# Sheet1.net
KiCad netlist of a schematic drawn in Altium Designer
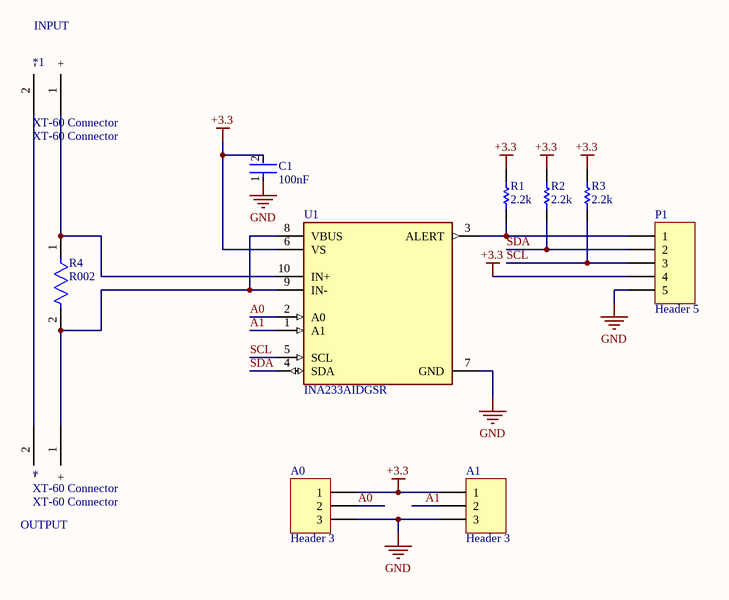
[diagram p0: Sheet1.SchDoc]

(export (version "E")
  (design (tool "Eeschema 10.0.6"))
  (components
    (comp (ref "*")
      (value "XT-60 Connector")
      (footprint "XT-60")
      (fields
        (field (name "MANUFACTURER") "POLOLU")
        (field (name "MANUFACTURER PART NUMBER") "XT60 YELLOW")
        (field (name "SUPPLIER PART NUMBER 1") "XT-60 Connector")
      )
      (libsource (lib "AltiumLibraryDDT") (part "XT-60 Connector"))
    )
    (comp (ref "*1")
      (value "XT-60 Connector")
      (footprint "XT-60")
      (fields
        (field (name "MANUFACTURER") "POLOLU")
        (field (name "MANUFACTURER PART NUMBER") "XT60 YELLOW")
        (field (name "SUPPLIER PART NUMBER 1") "XT-60 Connector")
      )
      (libsource (lib "AltiumLibraryDDT") (part "XT-60 Connector"))
    )
    (comp (ref "A0")
      (value "Header 3")
      (footprint "HDR1X3")
      (description "Header, 3-Pin")
      (fields (field (name "PUBLISHER") "Altium Limited"))
      (libsource (lib "") (part "Header 3_1"))
    )
    (comp (ref "A1")
      (value "Header 3")
      (footprint "HDR1X3")
      (description "Header, 3-Pin")
      (fields (field (name "PUBLISHER") "Altium Limited"))
      (libsource (lib "Miscellaneous Connectors") (part "Header 3"))
    )
    (comp (ref "C1")
      (value "100nF")
      (footprint "FP-0805-L_2_01_0_2-W_1_25-IPC_B")
      (description "General Purpose Ceramic Capacitor, 0805, 100nF, 10%, X7R, 15%, 100V")
      (fields (field (name "VOLTAGE") "100V") (field (name "TOLERANCE") "10%"))
      (libsource (lib "Altium Content Vault") (part "b4654b650e69147ec39a6b967a45e02"))
    )
    (comp (ref "P1")
      (value "Header 5")
      (footprint "HDR1X5")
      (description "Header, 5-Pin")
      (fields (field (name "PUBLISHER") "Altium Limited"))
      (libsource (lib "Miscellaneous Connectors") (part "Header 5"))
    )
    (comp (ref "R1")
      (value "2.2k")
      (footprint "RESC2013X60X35ML10T20")
      (fields (field (name "TOLERANCE") "5%") (field (name "MANUFACTURER") "Yageo"))
      (libsource (lib "Altium Content Vault") (part "RES-2"))
    )
    (comp (ref "R2")
      (value "2.2k")
      (footprint "RESC2013X60X35ML10T20")
      (fields (field (name "TOLERANCE") "5%") (field (name "MANUFACTURER") "Yageo"))
      (libsource (lib "Altium Content Vault") (part "RES-2"))
    )
    (comp (ref "R3")
      (value "2.2k")
      (footprint "RESC2013X60X35ML10T20")
      (fields (field (name "TOLERANCE") "5%") (field (name "MANUFACTURER") "Yageo"))
      (libsource (lib "Altium Content Vault") (part "RES-2"))
    )
    (comp (ref "R4")
      (value "R002")
      (footprint "FP-RL2512-MFG")
      (description "Thick Film Resistors - SMD 0.1ohm 1% 1W")
      (fields (field (name "OCTOPART") "https://octopart.com/rl2512fk-070r1l-yageo-42334369"))
      (libsource (lib "Altium Content Vault") (part "1029c3af85768c4190bb7ad29bc67b5"))
    )
    (comp (ref "U1")
      (value "INA233AIDGSR")
      (footprint "FP-DGS0010A-MFG")
      (libsource (lib "Altium Content Vault") (part "862aca6ea8ed29acc4669ae8acb3e69"))
    )
  )
  (nets
    (net (code "1") (name "+3.3") (class "Default")
      (node (ref "A0") (pin "1") (pinfunction "1_1") (pintype "passive"))
      (node (ref "A1") (pin "1") (pinfunction "1_1") (pintype "passive"))
      (node (ref "C1") (pin "2") (pinfunction "2_2") (pintype "passive"))
      (node (ref "P1") (pin "4") (pinfunction "4_4") (pintype "passive"))
      (node (ref "R1") (pin "2") (pinfunction "2_2") (pintype "passive"))
      (node (ref "R2") (pin "2") (pinfunction "2_2") (pintype "passive"))
      (node (ref "R3") (pin "2") (pinfunction "2_2") (pintype "passive"))
      (node (ref "U1") (pin "6") (pinfunction "VS_6") (pintype "power_in"))
    )
    (net (code "2") (name "/A0") (class "Default")
      (node (ref "A0") (pin "2") (pinfunction "2_2") (pintype "passive"))
      (node (ref "U1") (pin "2") (pinfunction "A0_2") (pintype "input"))
    )
    (net (code "3") (name "/A1") (class "Default")
      (node (ref "A1") (pin "2") (pinfunction "2_2") (pintype "passive"))
      (node (ref "U1") (pin "1") (pinfunction "A1_1") (pintype "input"))
    )
    (net (code "4") (name "/SCL") (class "Default")
      (node (ref "P1") (pin "3") (pinfunction "3_3") (pintype "passive"))
      (node (ref "R3") (pin "1") (pinfunction "1_1") (pintype "passive"))
      (node (ref "U1") (pin "5") (pinfunction "SCL_5") (pintype "input"))
    )
    (net (code "5") (name "/SDA") (class "Default")
      (node (ref "P1") (pin "2") (pinfunction "2_2") (pintype "passive"))
      (node (ref "R2") (pin "1") (pinfunction "1_1") (pintype "passive"))
      (node (ref "U1") (pin "4") (pinfunction "SDA_4") (pintype "bidirectional"))
    )
    (net (code "6") (name "GND") (class "Default")
      (node (ref "A0") (pin "3") (pinfunction "3_3") (pintype "passive"))
      (node (ref "A1") (pin "3") (pinfunction "3_3") (pintype "passive"))
      (node (ref "C1") (pin "1") (pinfunction "1_1") (pintype "passive"))
      (node (ref "P1") (pin "5") (pinfunction "5_5") (pintype "passive"))
      (node (ref "U1") (pin "7") (pinfunction "GND_7") (pintype "power_in"))
    )
    (net (code "7") (name "Net-(*-+)") (class "Default")
      (node (ref "*") (pin "1") (pinfunction "+_1") (pintype "power_in"))
      (node (ref "R4") (pin "2") (pinfunction "2_2") (pintype "passive"))
      (node (ref "U1") (pin "8") (pinfunction "VBUS_8") (pintype "power_in"))
      (node (ref "U1") (pin "9") (pinfunction "IN-_9") (pintype "tri_state"))
    )
    (net (code "8") (name "Net-(*--)") (class "Default")
      (node (ref "*") (pin "2") (pinfunction "-_2") (pintype "power_in"))
      (node (ref "*1") (pin "2") (pinfunction "-_2") (pintype "power_in"))
    )
    (net (code "9") (name "Net-(*1-+)") (class "Default")
      (node (ref "*1") (pin "1") (pinfunction "+_1") (pintype "power_in"))
      (node (ref "R4") (pin "1") (pinfunction "1_1") (pintype "passive"))
      (node (ref "U1") (pin "10") (pinfunction "IN+_10") (pintype "tri_state"))
    )
    (net (code "10") (name "Net-(U1-ALERT)") (class "Default")
      (node (ref "P1") (pin "1") (pinfunction "1_1") (pintype "passive"))
      (node (ref "R1") (pin "1") (pinfunction "1_1") (pintype "passive"))
      (node (ref "U1") (pin "3") (pinfunction "ALERT_3") (pintype "output"))
    )
  )
)
